# 1-6.net
KiCad netlist of a schematic drawn in EAGLE
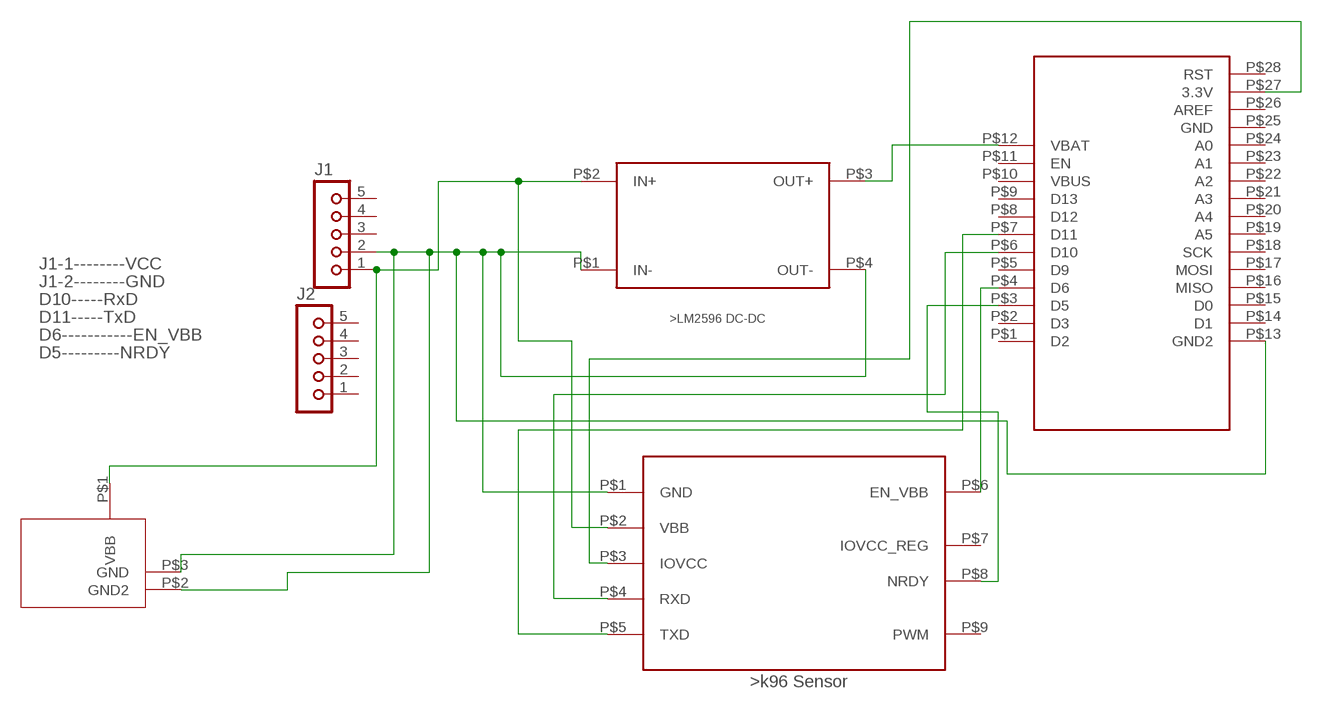
[diagram p0: schematic, sheet 1]

(export (version "E")
  (design (tool "Eeschema 10.0.6"))
  (components
    (comp (ref "DCDC1")
      (value "DCDC")
      (footprint "eagle-import:DCDC")
      (libsource (lib "eagle-import") (part "DCDC"))
    )
    (comp (ref "FEATHER1")
      (value "FEATHER")
      (footprint "eagle-import:FEATHER")
      (libsource (lib "eagle-import") (part "FEATHER"))
    )
    (comp (ref "J1")
      (value "JU05")
      (footprint "eagle-import:JU05")
      (libsource (lib "eagle-import") (part "JU05"))
    )
    (comp (ref "J2")
      (value "JU05")
      (footprint "eagle-import:JU05")
      (libsource (lib "eagle-import") (part "JU05"))
    )
    (comp (ref "K96SENSOR1")
      (value "K96SENSOR")
      (footprint "eagle-import:K96SENSOR")
      (libsource (lib "eagle-import") (part "K96SENSOR"))
    )
    (comp (ref "U$2")
      (value "POWER")
      (footprint "eagle-import:POWERIN")
      (libsource (lib "eagle-import") (part "POWER"))
    )
  )
  (nets
    (net (code "1") (name "Net-(DCDC1-IN+)") (class "Default")
      (node (ref "DCDC1") (pin "P$2") (pinfunction "IN+_P$2") (pintype "bidirectional"))
      (node (ref "J1") (pin "1") (pinfunction "1_1") (pintype "passive"))
      (node (ref "K96SENSOR1") (pin "P$2") (pinfunction "VBB_P$2") (pintype "bidirectional"))
      (node (ref "U$2") (pin "P$1") (pinfunction "VBB_P$1") (pintype "bidirectional"))
    )
    (net (code "2") (name "Net-(DCDC1-IN-)") (class "Default")
      (node (ref "DCDC1") (pin "P$1") (pinfunction "IN-_P$1") (pintype "bidirectional"))
      (node (ref "DCDC1") (pin "P$4") (pinfunction "OUT-_P$4") (pintype "bidirectional"))
      (node (ref "FEATHER1") (pin "P$13") (pinfunction "GND2_P$13") (pintype "bidirectional"))
      (node (ref "J1") (pin "2") (pinfunction "2_2") (pintype "passive"))
      (node (ref "K96SENSOR1") (pin "P$1") (pinfunction "GND_P$1") (pintype "bidirectional"))
      (node (ref "U$2") (pin "P$2") (pinfunction "GND2_P$2") (pintype "bidirectional"))
      (node (ref "U$2") (pin "P$3") (pinfunction "GND_P$3") (pintype "bidirectional"))
    )
    (net (code "3") (name "Net-(DCDC1-OUT+)") (class "Default")
      (node (ref "DCDC1") (pin "P$3") (pinfunction "OUT+_P$3") (pintype "bidirectional"))
      (node (ref "FEATHER1") (pin "P$12") (pinfunction "VBAT_P$12") (pintype "bidirectional"))
    )
    (net (code "4") (name "Net-(FEATHER1-3.3V)") (class "Default")
      (node (ref "FEATHER1") (pin "P$27") (pinfunction "3.3V_P$27") (pintype "bidirectional"))
      (node (ref "K96SENSOR1") (pin "P$3") (pinfunction "IOVCC_P$3") (pintype "bidirectional"))
    )
    (net (code "5") (name "Net-(FEATHER1-D5)") (class "Default")
      (node (ref "FEATHER1") (pin "P$3") (pinfunction "D5_P$3") (pintype "bidirectional"))
      (node (ref "K96SENSOR1") (pin "P$8") (pinfunction "NRDY_P$8") (pintype "bidirectional"))
    )
    (net (code "6") (name "Net-(FEATHER1-D6)") (class "Default")
      (node (ref "FEATHER1") (pin "P$4") (pinfunction "D6_P$4") (pintype "bidirectional"))
      (node (ref "K96SENSOR1") (pin "P$6") (pinfunction "EN_VBB_P$6") (pintype "bidirectional"))
    )
    (net (code "7") (name "Net-(FEATHER1-D10)") (class "Default")
      (node (ref "FEATHER1") (pin "P$6") (pinfunction "D10_P$6") (pintype "bidirectional"))
      (node (ref "K96SENSOR1") (pin "P$4") (pinfunction "RXD_P$4") (pintype "bidirectional"))
    )
    (net (code "8") (name "Net-(FEATHER1-D11)") (class "Default")
      (node (ref "FEATHER1") (pin "P$7") (pinfunction "D11_P$7") (pintype "bidirectional"))
      (node (ref "K96SENSOR1") (pin "P$5") (pinfunction "TXD_P$5") (pintype "bidirectional"))
    )
    (net (code "9") (name "unconnected-(FEATHER1-A0-PadP$24)") (class "Default")
      (node (ref "FEATHER1") (pin "P$24") (pinfunction "A0_P$24") (pintype "bidirectional"))
    )
    (net (code "10") (name "unconnected-(FEATHER1-A1-PadP$23)") (class "Default")
      (node (ref "FEATHER1") (pin "P$23") (pinfunction "A1_P$23") (pintype "bidirectional"))
    )
    (net (code "11") (name "unconnected-(FEATHER1-A2-PadP$22)") (class "Default")
      (node (ref "FEATHER1") (pin "P$22") (pinfunction "A2_P$22") (pintype "bidirectional"))
    )
    (net (code "12") (name "unconnected-(FEATHER1-A3-PadP$21)") (class "Default")
      (node (ref "FEATHER1") (pin "P$21") (pinfunction "A3_P$21") (pintype "bidirectional"))
    )
    (net (code "13") (name "unconnected-(FEATHER1-A4-PadP$20)") (class "Default")
      (node (ref "FEATHER1") (pin "P$20") (pinfunction "A4_P$20") (pintype "bidirectional"))
    )
    (net (code "14") (name "unconnected-(FEATHER1-A5-PadP$19)") (class "Default")
      (node (ref "FEATHER1") (pin "P$19") (pinfunction "A5_P$19") (pintype "bidirectional"))
    )
    (net (code "15") (name "unconnected-(FEATHER1-AREF-PadP$26)") (class "Default")
      (node (ref "FEATHER1") (pin "P$26") (pinfunction "AREF_P$26") (pintype "bidirectional"))
    )
    (net (code "16") (name "unconnected-(FEATHER1-D0-PadP$15)") (class "Default")
      (node (ref "FEATHER1") (pin "P$15") (pinfunction "D0_P$15") (pintype "bidirectional"))
    )
    (net (code "17") (name "unconnected-(FEATHER1-D1-PadP$14)") (class "Default")
      (node (ref "FEATHER1") (pin "P$14") (pinfunction "D1_P$14") (pintype "bidirectional"))
    )
    (net (code "18") (name "unconnected-(FEATHER1-D2-PadP$1)") (class "Default")
      (node (ref "FEATHER1") (pin "P$1") (pinfunction "D2_P$1") (pintype "bidirectional"))
    )
    (net (code "19") (name "unconnected-(FEATHER1-D3-PadP$2)") (class "Default")
      (node (ref "FEATHER1") (pin "P$2") (pinfunction "D3_P$2") (pintype "bidirectional"))
    )
    (net (code "20") (name "unconnected-(FEATHER1-D9-PadP$5)") (class "Default")
      (node (ref "FEATHER1") (pin "P$5") (pinfunction "D9_P$5") (pintype "bidirectional"))
    )
    (net (code "21") (name "unconnected-(FEATHER1-D12-PadP$8)") (class "Default")
      (node (ref "FEATHER1") (pin "P$8") (pinfunction "D12_P$8") (pintype "bidirectional"))
    )
    (net (code "22") (name "unconnected-(FEATHER1-D13-PadP$9)") (class "Default")
      (node (ref "FEATHER1") (pin "P$9") (pinfunction "D13_P$9") (pintype "bidirectional"))
    )
    (net (code "23") (name "unconnected-(FEATHER1-EN-PadP$11)") (class "Default")
      (node (ref "FEATHER1") (pin "P$11") (pinfunction "EN_P$11") (pintype "bidirectional"))
    )
    (net (code "24") (name "unconnected-(FEATHER1-GND-PadP$25)") (class "Default")
      (node (ref "FEATHER1") (pin "P$25") (pinfunction "GND_P$25") (pintype "bidirectional"))
    )
    (net (code "25") (name "unconnected-(FEATHER1-MISO-PadP$16)") (class "Default")
      (node (ref "FEATHER1") (pin "P$16") (pinfunction "MISO_P$16") (pintype "bidirectional"))
    )
    (net (code "26") (name "unconnected-(FEATHER1-MOSI-PadP$17)") (class "Default")
      (node (ref "FEATHER1") (pin "P$17") (pinfunction "MOSI_P$17") (pintype "bidirectional"))
    )
    (net (code "27") (name "unconnected-(FEATHER1-RST-PadP$28)") (class "Default")
      (node (ref "FEATHER1") (pin "P$28") (pinfunction "RST_P$28") (pintype "bidirectional"))
    )
    (net (code "28") (name "unconnected-(FEATHER1-SCK-PadP$18)") (class "Default")
      (node (ref "FEATHER1") (pin "P$18") (pinfunction "SCK_P$18") (pintype "bidirectional"))
    )
    (net (code "29") (name "unconnected-(FEATHER1-VBUS-PadP$10)") (class "Default")
      (node (ref "FEATHER1") (pin "P$10") (pinfunction "VBUS_P$10") (pintype "bidirectional"))
    )
    (net (code "30") (name "unconnected-(J1-Pad3)") (class "Default")
      (node (ref "J1") (pin "3") (pinfunction "3_3") (pintype "passive"))
    )
    (net (code "31") (name "unconnected-(J1-Pad4)") (class "Default")
      (node (ref "J1") (pin "4") (pinfunction "4_4") (pintype "passive"))
    )
    (net (code "32") (name "unconnected-(J1-Pad5)") (class "Default")
      (node (ref "J1") (pin "5") (pinfunction "5_5") (pintype "passive"))
    )
    (net (code "33") (name "unconnected-(J2-Pad1)") (class "Default")
      (node (ref "J2") (pin "1") (pinfunction "1_1") (pintype "passive"))
    )
    (net (code "34") (name "unconnected-(J2-Pad2)") (class "Default")
      (node (ref "J2") (pin "2") (pinfunction "2_2") (pintype "passive"))
    )
    (net (code "35") (name "unconnected-(J2-Pad3)") (class "Default")
      (node (ref "J2") (pin "3") (pinfunction "3_3") (pintype "passive"))
    )
    (net (code "36") (name "unconnected-(J2-Pad4)") (class "Default")
      (node (ref "J2") (pin "4") (pinfunction "4_4") (pintype "passive"))
    )
    (net (code "37") (name "unconnected-(J2-Pad5)") (class "Default")
      (node (ref "J2") (pin "5") (pinfunction "5_5") (pintype "passive"))
    )
    (net (code "38") (name "unconnected-(K96SENSOR1-IOVCC_REG-PadP$7)") (class "Default")
      (node (ref "K96SENSOR1") (pin "P$7") (pinfunction "IOVCC_REG_P$7") (pintype "bidirectional"))
    )
    (net (code "39") (name "unconnected-(K96SENSOR1-PWM-PadP$9)") (class "Default")
      (node (ref "K96SENSOR1") (pin "P$9") (pinfunction "PWM_P$9") (pintype "bidirectional"))
    )
  )
)
